# Button.net
KiCad netlist of a schematic drawn in EAGLE
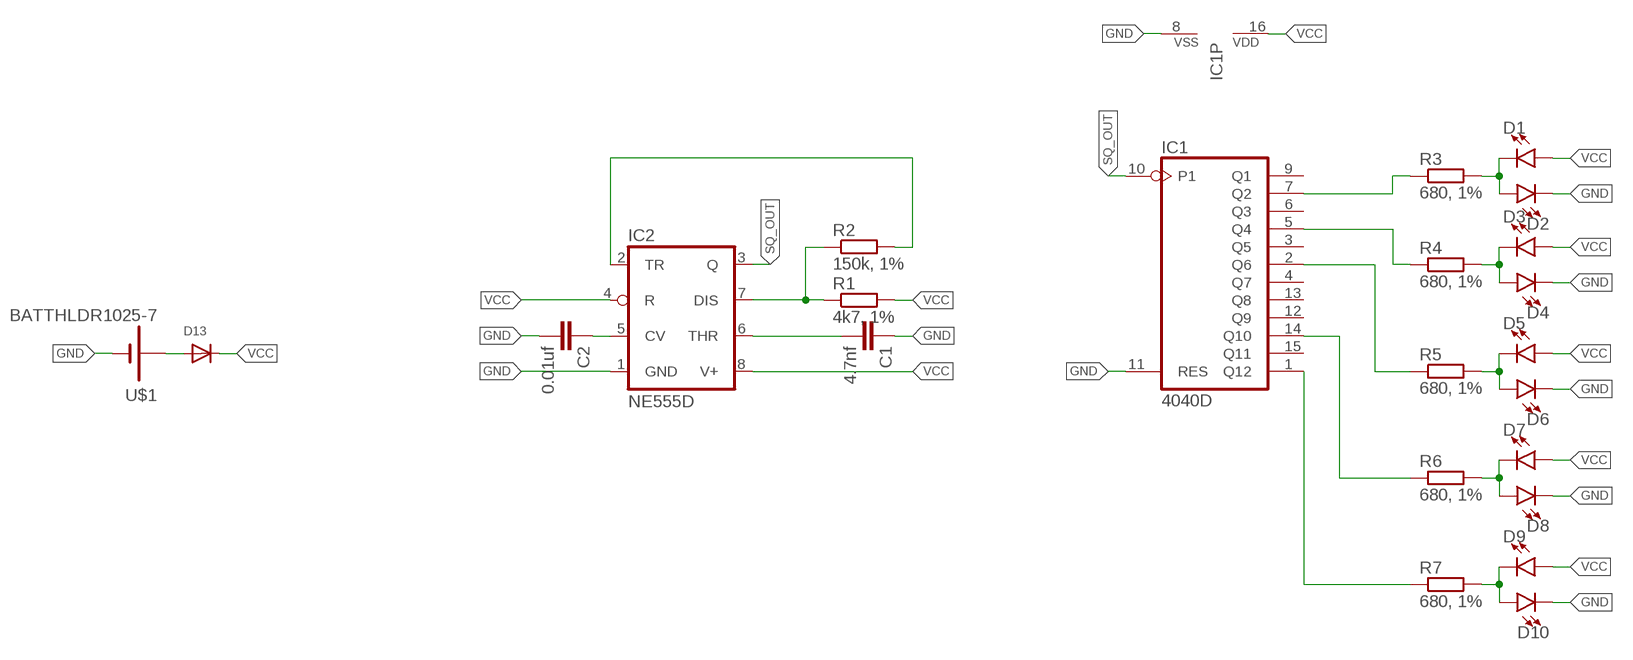
[diagram p0: schematic, sheet 1]

(export (version "E")
  (design (tool "Eeschema 10.0.6"))
  (components
    (comp (ref "C1")
      (value "4.7nf")
      (footprint "eagle-import:C1206")
      (libsource (lib "eagle-import") (part "C-EUC1206"))
    )
    (comp (ref "C2")
      (value "0.01uf")
      (footprint "eagle-import:C1206")
      (libsource (lib "eagle-import") (part "C-EUC1206"))
    )
    (comp (ref "D1")
      (value "LED1206")
      (footprint "eagle-import:LED-1206")
      (libsource (lib "eagle-import") (part "LED1206"))
    )
    (comp (ref "D2")
      (value "LED1206")
      (footprint "eagle-import:LED-1206")
      (libsource (lib "eagle-import") (part "LED1206"))
    )
    (comp (ref "D3")
      (value "LED1206")
      (footprint "eagle-import:LED-1206")
      (libsource (lib "eagle-import") (part "LED1206"))
    )
    (comp (ref "D4")
      (value "LED1206")
      (footprint "eagle-import:LED-1206")
      (libsource (lib "eagle-import") (part "LED1206"))
    )
    (comp (ref "D5")
      (value "LED1206")
      (footprint "eagle-import:LED-1206")
      (libsource (lib "eagle-import") (part "LED1206"))
    )
    (comp (ref "D6")
      (value "LED1206")
      (footprint "eagle-import:LED-1206")
      (libsource (lib "eagle-import") (part "LED1206"))
    )
    (comp (ref "D7")
      (value "LED1206")
      (footprint "eagle-import:LED-1206")
      (libsource (lib "eagle-import") (part "LED1206"))
    )
    (comp (ref "D8")
      (value "LED1206")
      (footprint "eagle-import:LED-1206")
      (libsource (lib "eagle-import") (part "LED1206"))
    )
    (comp (ref "D9")
      (value "LED1206")
      (footprint "eagle-import:LED-1206")
      (libsource (lib "eagle-import") (part "LED1206"))
    )
    (comp (ref "D10")
      (value "LED1206")
      (footprint "eagle-import:LED-1206")
      (libsource (lib "eagle-import") (part "LED1206"))
    )
    (comp (ref "D13")
      (value "DIODESMA")
      (footprint "eagle-import:SMADIODE")
      (libsource (lib "eagle-import") (part "DIODESMA"))
    )
    (comp (ref "IC1")
      (value "4040D")
      (footprint "eagle-import:SO16")
      (libsource (lib "eagle-import") (part "4040D"))
    )
    (comp (ref "IC2")
      (value "NE555D")
      (footprint "eagle-import:SO08")
      (libsource (lib "eagle-import") (part "555DNE"))
    )
    (comp (ref "R1")
      (value "4k7, 1%")
      (footprint "eagle-import:R1206")
      (libsource (lib "eagle-import") (part "R-EU_R1206"))
    )
    (comp (ref "R2")
      (value "150k, 1%")
      (footprint "eagle-import:R1206")
      (libsource (lib "eagle-import") (part "R-EU_R1206"))
    )
    (comp (ref "R3")
      (value "680, 1%")
      (footprint "eagle-import:R1206")
      (libsource (lib "eagle-import") (part "R-EU_R1206"))
    )
    (comp (ref "R4")
      (value "680, 1%")
      (footprint "eagle-import:R1206")
      (libsource (lib "eagle-import") (part "R-EU_R1206"))
    )
    (comp (ref "R5")
      (value "680, 1%")
      (footprint "eagle-import:R1206")
      (libsource (lib "eagle-import") (part "R-EU_R1206"))
    )
    (comp (ref "R6")
      (value "680, 1%")
      (footprint "eagle-import:R1206")
      (libsource (lib "eagle-import") (part "R-EU_R1206"))
    )
    (comp (ref "R7")
      (value "680, 1%")
      (footprint "eagle-import:R1206")
      (libsource (lib "eagle-import") (part "R-EU_R1206"))
    )
    (comp (ref "U$1")
      (value "BATTHLDR1025-7")
      (footprint "eagle-import:BATTHLDR1025-7")
      (libsource (lib "eagle-import") (part "BATTHLDR1025-7"))
    )
  )
  (nets
    (net (code "1") (name "GND") (class "Default")
      (node (ref "C1") (pin "1") (pinfunction "1_1") (pintype "passive"))
      (node (ref "C2") (pin "2") (pinfunction "2_2") (pintype "passive"))
      (node (ref "D10") (pin "C") (pinfunction "C_C") (pintype "passive"))
      (node (ref "D2") (pin "C") (pinfunction "C_C") (pintype "passive"))
      (node (ref "D4") (pin "C") (pinfunction "C_C") (pintype "passive"))
      (node (ref "D6") (pin "C") (pinfunction "C_C") (pintype "passive"))
      (node (ref "D8") (pin "C") (pinfunction "C_C") (pintype "passive"))
      (node (ref "IC1") (pin "11") (pinfunction "RES_11") (pintype "input"))
      (node (ref "IC1") (pin "8") (pinfunction "VSS_8") (pintype "power_in"))
      (node (ref "IC2") (pin "1") (pinfunction "GND_1") (pintype "power_in"))
      (node (ref "U$1") (pin "NEGATIVE") (pinfunction "-_NEGATIVE") (pintype "power_in"))
    )
    (net (code "2") (name "Net-(D1-PadC)") (class "Default")
      (node (ref "D1") (pin "C") (pinfunction "C_C") (pintype "passive"))
      (node (ref "D2") (pin "A") (pinfunction "A_A") (pintype "passive"))
      (node (ref "R3") (pin "2") (pinfunction "2_2") (pintype "passive"))
    )
    (net (code "3") (name "Net-(D3-PadC)") (class "Default")
      (node (ref "D3") (pin "C") (pinfunction "C_C") (pintype "passive"))
      (node (ref "D4") (pin "A") (pinfunction "A_A") (pintype "passive"))
      (node (ref "R4") (pin "2") (pinfunction "2_2") (pintype "passive"))
    )
    (net (code "4") (name "Net-(D5-PadC)") (class "Default")
      (node (ref "D5") (pin "C") (pinfunction "C_C") (pintype "passive"))
      (node (ref "D6") (pin "A") (pinfunction "A_A") (pintype "passive"))
      (node (ref "R5") (pin "2") (pinfunction "2_2") (pintype "passive"))
    )
    (net (code "5") (name "Net-(D7-PadC)") (class "Default")
      (node (ref "D7") (pin "C") (pinfunction "C_C") (pintype "passive"))
      (node (ref "D8") (pin "A") (pinfunction "A_A") (pintype "passive"))
      (node (ref "R6") (pin "2") (pinfunction "2_2") (pintype "passive"))
    )
    (net (code "6") (name "Net-(D10-PadA)") (class "Default")
      (node (ref "D10") (pin "A") (pinfunction "A_A") (pintype "passive"))
      (node (ref "D9") (pin "C") (pinfunction "C_C") (pintype "passive"))
      (node (ref "R7") (pin "2") (pinfunction "2_2") (pintype "passive"))
    )
    (net (code "7") (name "Net-(IC1A-Q2)") (class "Default")
      (node (ref "IC1") (pin "7") (pinfunction "Q2_7") (pintype "output"))
      (node (ref "R3") (pin "1") (pinfunction "1_1") (pintype "passive"))
    )
    (net (code "8") (name "Net-(IC1A-Q4)") (class "Default")
      (node (ref "IC1") (pin "5") (pinfunction "Q4_5") (pintype "output"))
      (node (ref "R4") (pin "1") (pinfunction "1_1") (pintype "passive"))
    )
    (net (code "9") (name "Net-(IC1A-Q6)") (class "Default")
      (node (ref "IC1") (pin "2") (pinfunction "Q6_2") (pintype "output"))
      (node (ref "R5") (pin "1") (pinfunction "1_1") (pintype "passive"))
    )
    (net (code "10") (name "Net-(IC1A-Q10)") (class "Default")
      (node (ref "IC1") (pin "14") (pinfunction "Q10_14") (pintype "output"))
      (node (ref "R6") (pin "1") (pinfunction "1_1") (pintype "passive"))
    )
    (net (code "11") (name "Net-(IC1A-Q12)") (class "Default")
      (node (ref "IC1") (pin "1") (pinfunction "Q12_1") (pintype "output"))
      (node (ref "R7") (pin "1") (pinfunction "1_1") (pintype "passive"))
    )
    (net (code "12") (name "Net-(IC2-CV)") (class "Default")
      (node (ref "C2") (pin "1") (pinfunction "1_1") (pintype "passive"))
      (node (ref "IC2") (pin "5") (pinfunction "CV_5") (pintype "input"))
    )
    (net (code "13") (name "Net-(IC2-DIS)") (class "Default")
      (node (ref "IC2") (pin "7") (pinfunction "DIS_7") (pintype "input"))
      (node (ref "R1") (pin "1") (pinfunction "1_1") (pintype "passive"))
      (node (ref "R2") (pin "1") (pinfunction "1_1") (pintype "passive"))
    )
    (net (code "14") (name "Net-(IC2-THR)") (class "Default")
      (node (ref "C1") (pin "2") (pinfunction "2_2") (pintype "passive"))
      (node (ref "IC2") (pin "6") (pinfunction "THR_6") (pintype "input"))
    )
    (net (code "15") (name "Net-(IC2-TR)") (class "Default")
      (node (ref "IC2") (pin "2") (pinfunction "TR_2") (pintype "input"))
      (node (ref "R2") (pin "2") (pinfunction "2_2") (pintype "passive"))
    )
    (net (code "16") (name "Net-(U$1-+)") (class "Default")
      (node (ref "D13") (pin "A") (pinfunction "A_A") (pintype "passive"))
      (node (ref "U$1") (pin "POSITIVE") (pinfunction "+_POSITIVE") (pintype "power_in"))
    )
    (net (code "17") (name "SQ_OUT") (class "Default")
      (node (ref "IC1") (pin "10") (pinfunction "P1_10") (pintype "input"))
      (node (ref "IC2") (pin "3") (pinfunction "Q_3") (pintype "output"))
    )
    (net (code "18") (name "VCC") (class "Default")
      (node (ref "D1") (pin "A") (pinfunction "A_A") (pintype "passive"))
      (node (ref "D13") (pin "C") (pinfunction "C_C") (pintype "passive"))
      (node (ref "D3") (pin "A") (pinfunction "A_A") (pintype "passive"))
      (node (ref "D5") (pin "A") (pinfunction "A_A") (pintype "passive"))
      (node (ref "D7") (pin "A") (pinfunction "A_A") (pintype "passive"))
      (node (ref "D9") (pin "A") (pinfunction "A_A") (pintype "passive"))
      (node (ref "IC1") (pin "16") (pinfunction "VDD_16") (pintype "power_in"))
      (node (ref "IC2") (pin "4") (pinfunction "R_4") (pintype "input"))
      (node (ref "IC2") (pin "8") (pinfunction "V+_8") (pintype "power_in"))
      (node (ref "R1") (pin "2") (pinfunction "2_2") (pintype "passive"))
    )
    (net (code "19") (name "unconnected-(IC1A-Q1-Pad9)") (class "Default")
      (node (ref "IC1") (pin "9") (pinfunction "Q1_9") (pintype "output"))
    )
    (net (code "20") (name "unconnected-(IC1A-Q3-Pad6)") (class "Default")
      (node (ref "IC1") (pin "6") (pinfunction "Q3_6") (pintype "output"))
    )
    (net (code "21") (name "unconnected-(IC1A-Q5-Pad3)") (class "Default")
      (node (ref "IC1") (pin "3") (pinfunction "Q5_3") (pintype "output"))
    )
    (net (code "22") (name "unconnected-(IC1A-Q7-Pad4)") (class "Default")
      (node (ref "IC1") (pin "4") (pinfunction "Q7_4") (pintype "output"))
    )
    (net (code "23") (name "unconnected-(IC1A-Q8-Pad13)") (class "Default")
      (node (ref "IC1") (pin "13") (pinfunction "Q8_13") (pintype "output"))
    )
    (net (code "24") (name "unconnected-(IC1A-Q9-Pad12)") (class "Default")
      (node (ref "IC1") (pin "12") (pinfunction "Q9_12") (pintype "output"))
    )
    (net (code "25") (name "unconnected-(IC1A-Q11-Pad15)") (class "Default")
      (node (ref "IC1") (pin "15") (pinfunction "Q11_15") (pintype "output"))
    )
  )
)
